# KL_Link.net
KiCad netlist of a schematic drawn in Altium Designer
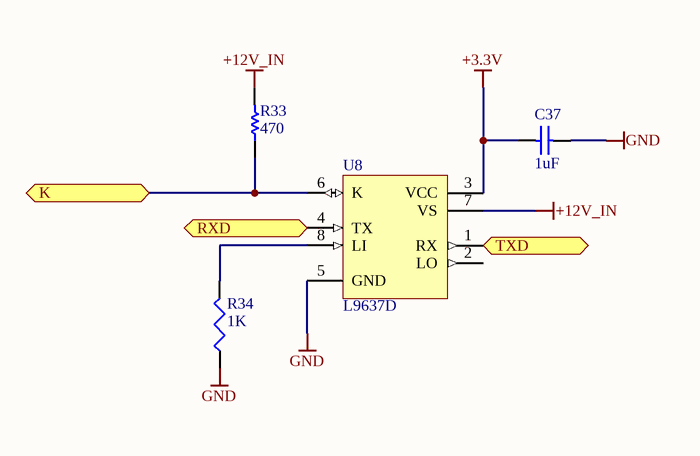
[diagram p0: KL Link.SchDoc]

(export (version "E")
  (design (tool "Eeschema 10.0.6"))
  (components
    (comp (ref "C37")
      (value "1uF")
      (footprint "2012[0805]")
      (description "Ceramic Chip Capacitor - Standard")
      (fields (field (name "PUBLISHER") "Altium Limited"))
      (libsource (lib "ResAndCaps") (part "C0805"))
    )
    (comp (ref "R33")
      (value "470")
      (footprint "6332[2512]")
      (description "Resistor")
      (fields (field (name "PUBLISHER") "Altium Limited"))
      (libsource (lib "Miscellaneous Devices") (part "Res1"))
    )
    (comp (ref "R34")
      (value "1K")
      (footprint "R2012[0805]")
      (description "R0805")
      (fields (field (name "PUBLISHER") "Altium Limited"))
      (libsource (lib "ResAndCaps") (part "R0805"))
    )
    (comp (ref "U8")
      (value "L9637D")
      (footprint "SO8_N")
      (description "ISO 9141 Interface")
      (fields (field (name "PUBLISHER") "Altium Limited"))
      (libsource (lib "ST Automotive Diagnostic Serial Link") (part "L9637D"))
    )
  )
  (nets
    (net (code "1") (name "+3.3V") (class "Default")
      (node (ref "C37") (pin "1") (pinfunction "1_1") (pintype "passive"))
      (node (ref "U8") (pin "3") (pinfunction "VCC_3") (pintype "power_in"))
    )
    (net (code "2") (name "+12V_IN") (class "Default")
      (node (ref "R33") (pin "2") (pinfunction "2_2") (pintype "passive"))
      (node (ref "U8") (pin "7") (pinfunction "VS_7") (pintype "power_in"))
    )
    (net (code "3") (name "/K") (class "Default")
      (node (ref "R33") (pin "1") (pinfunction "1_1") (pintype "passive"))
      (node (ref "U8") (pin "6") (pinfunction "K_6") (pintype "bidirectional"))
    )
    (net (code "4") (name "/RXD") (class "Default")
      (node (ref "U8") (pin "4") (pinfunction "TX_4") (pintype "input"))
    )
    (net (code "5") (name "/TXD") (class "Default")
      (node (ref "U8") (pin "1") (pinfunction "RX_1") (pintype "output"))
    )
    (net (code "6") (name "GND") (class "Default")
      (node (ref "C37") (pin "2") (pinfunction "2_2") (pintype "passive"))
      (node (ref "R34") (pin "1") (pinfunction "1_1") (pintype "passive"))
      (node (ref "U8") (pin "5") (pinfunction "GND_5") (pintype "power_in"))
    )
    (net (code "7") (name "Net-(U8-LI)") (class "Default")
      (node (ref "R34") (pin "2") (pinfunction "2_2") (pintype "passive"))
      (node (ref "U8") (pin "8") (pinfunction "LI_8") (pintype "input"))
    )
    (net (code "8") (name "unconnected-(U8-LO-Pad2)") (class "Default")
      (node (ref "U8") (pin "2") (pinfunction "LO_2") (pintype "output"))
    )
  )
)
